# ProDoc_simpleCH552_typeA_finished.net
KiCad netlist of a schematic drawn in EasyEDA Pro
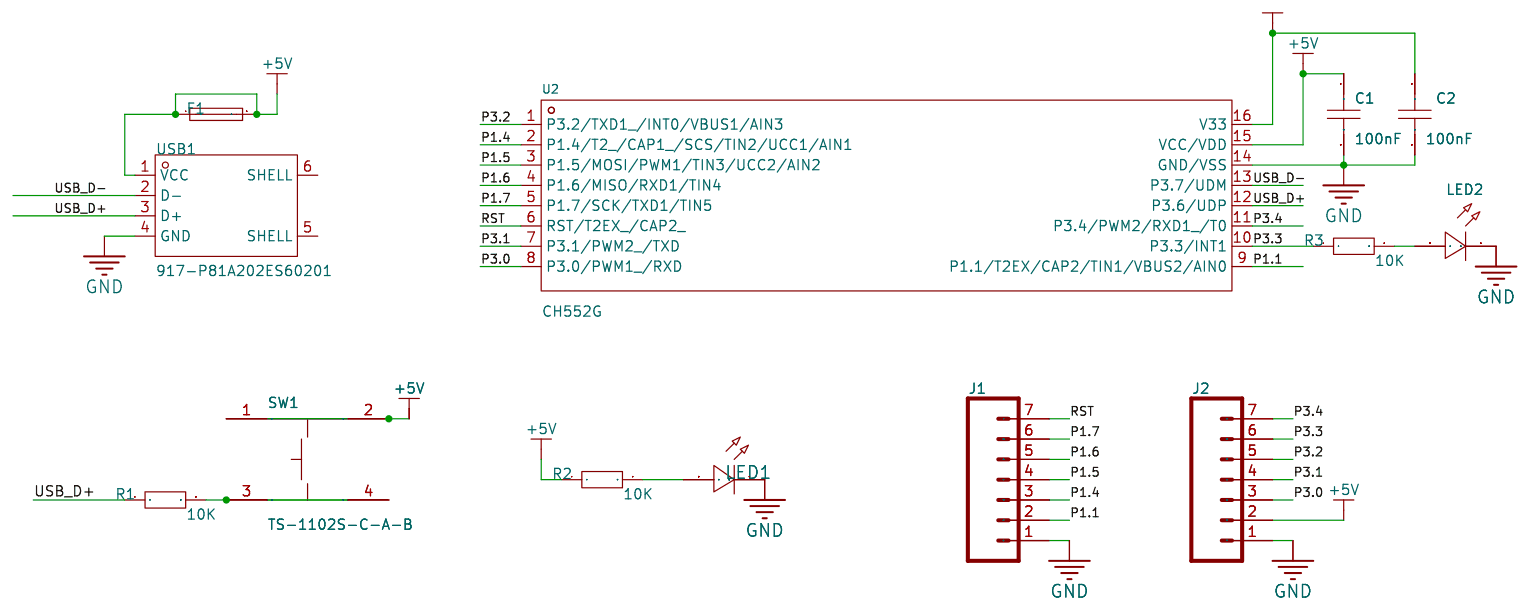
[diagram p0: schematic sheet]

(export (version "E")
  (design (tool "Eeschema 10.0.6"))
  (components
    (comp (ref "C1")
      (value "100nF")
      (footprint "easyedapro:C0805")
      (libsource (lib "easyedapro") (part "CAP"))
    )
    (comp (ref "C2")
      (value "100nF")
      (footprint "easyedapro:C0805")
      (libsource (lib "easyedapro") (part "CAP"))
    )
    (comp (ref "F1")
      (value "SF-1206S080-2")
      (footprint "easyedapro:F1206")
      (fields (field (name "Manufacturer") "BOURNS"))
      (libsource (lib "easyedapro") (part "SF-1206S080-2"))
    )
    (comp (ref "J1")
      (value "CONN_07NO_SILK")
      (footprint "easyedapro:1X07_NO_SILK")
      (libsource (lib "easyedapro") (part "SparkFun-Connectors_CONN_07_NO_SILK"))
    )
    (comp (ref "J2")
      (value "CONN_07NO_SILK")
      (footprint "easyedapro:1X07_NO_SILK")
      (libsource (lib "easyedapro") (part "SparkFun-Connectors_CONN_07_NO_SILK"))
    )
    (comp (ref "LED1")
      (value "~")
      (footprint "easyedapro:LED0805-RD_GREEN")
      (libsource (lib "easyedapro") (part "LED_R"))
    )
    (comp (ref "LED2")
      (value "~")
      (footprint "easyedapro:LED0805-RD_GREEN")
      (libsource (lib "easyedapro") (part "LED_G"))
    )
    (comp (ref "R1") (value "10K") (footprint "easyedapro:R0805") (libsource (lib "easyedapro") (part "Res")))
    (comp (ref "R2") (value "10K") (footprint "easyedapro:R0805") (libsource (lib "easyedapro") (part "Res")))
    (comp (ref "R3") (value "10K") (footprint "easyedapro:R0805") (libsource (lib "easyedapro") (part "Res")))
    (comp (ref "SW1")
      (value "TS-1102S-C-A-B")
      (footprint "easyedapro:KEY-SMD_4P-L6.0-W6.0-P4.50-LS8.6")
      (fields (field (name "Manufacturer") "XKB Connection(中国星坤)"))
      (libsource (lib "easyedapro") (part "TS-1102S-C-A-B"))
    )
    (comp (ref "U2")
      (value "CH552G")
      (footprint "easyedapro:SOP-16_L10.0-W3.9-P1.27-LS6.0-BL")
      (fields (field (name "Manufacturer") "WCH(南京沁恒)"))
      (libsource (lib "easyedapro") (part "CH552G"))
    )
    (comp (ref "USB1")
      (value "917-P81A202ES60201")
      (footprint "easyedapro:USB-A-SMD_917-P81A202ES60201")
      (fields (field (name "Manufacturer") "精拓金"))
      (libsource (lib "easyedapro") (part "917-P81A202ES60201"))
    )
  )
  (nets
    (net (code "1") (name "+5V") (class "Default")
      (node (ref "C1") (pin "1") (pinfunction "1_1") (pintype "input"))
      (node (ref "F1") (pin "1") (pinfunction "1_1") (pintype "unspecified"))
      (node (ref "F1") (pin "2") (pinfunction "2_2") (pintype "unspecified"))
      (node (ref "J2") (pin "2") (pinfunction "2_2") (pintype "unspecified"))
      (node (ref "R2") (pin "1") (pinfunction "1_1") (pintype "input"))
      (node (ref "SW1") (pin "1") (pinfunction "1_1") (pintype "unspecified"))
      (node (ref "SW1") (pin "2") (pinfunction "2_2") (pintype "unspecified"))
      (node (ref "U2") (pin "15") (pinfunction "VCC/VDD_15") (pintype "input"))
      (node (ref "USB1") (pin "1") (pinfunction "VCC_1") (pintype "unspecified"))
    )
    (net (code "2") (name "/P1.1") (class "Default")
      (node (ref "J1") (pin "2") (pinfunction "2_2") (pintype "unspecified"))
      (node (ref "U2") (pin "9") (pinfunction "P1.1/T2EX/CAP2/TIN1/VBUS2/AIN0_9") (pintype "input"))
    )
    (net (code "3") (name "/P1.4") (class "Default")
      (node (ref "J1") (pin "3") (pinfunction "3_3") (pintype "unspecified"))
      (node (ref "U2") (pin "2") (pinfunction "P1.4/T2_/CAP1_/SCS/TIN2/UCC1/AIN1_2") (pintype "input"))
    )
    (net (code "4") (name "/P1.5") (class "Default")
      (node (ref "J1") (pin "4") (pinfunction "4_4") (pintype "unspecified"))
      (node (ref "U2") (pin "3") (pinfunction "P1.5/MOSI/PWM1/TIN3/UCC2/AIN2_3") (pintype "input"))
    )
    (net (code "5") (name "/P1.6") (class "Default")
      (node (ref "J1") (pin "5") (pinfunction "5_5") (pintype "unspecified"))
      (node (ref "U2") (pin "4") (pinfunction "P1.6/MISO/RXD1/TIN4_4") (pintype "input"))
    )
    (net (code "6") (name "/P1.7") (class "Default")
      (node (ref "J1") (pin "6") (pinfunction "6_6") (pintype "unspecified"))
      (node (ref "U2") (pin "5") (pinfunction "P1.7/SCK/TXD1/TIN5_5") (pintype "input"))
    )
    (net (code "7") (name "/P3.0") (class "Default")
      (node (ref "J2") (pin "3") (pinfunction "3_3") (pintype "unspecified"))
      (node (ref "U2") (pin "8") (pinfunction "P3.0/PWM1_/RXD_8") (pintype "input"))
    )
    (net (code "8") (name "/P3.1") (class "Default")
      (node (ref "J2") (pin "4") (pinfunction "4_4") (pintype "unspecified"))
      (node (ref "U2") (pin "7") (pinfunction "P3.1/PWM2_/TXD_7") (pintype "input"))
    )
    (net (code "9") (name "/P3.2") (class "Default")
      (node (ref "J2") (pin "5") (pinfunction "5_5") (pintype "unspecified"))
      (node (ref "U2") (pin "1") (pinfunction "P3.2/TXD1_/INT0/VBUS1/AIN3_1") (pintype "input"))
    )
    (net (code "10") (name "/P3.3") (class "Default")
      (node (ref "J2") (pin "6") (pinfunction "6_6") (pintype "unspecified"))
      (node (ref "R3") (pin "1") (pinfunction "1_1") (pintype "input"))
      (node (ref "U2") (pin "10") (pinfunction "P3.3/INT1_10") (pintype "input"))
    )
    (net (code "11") (name "/P3.4") (class "Default")
      (node (ref "J2") (pin "7") (pinfunction "7_7") (pintype "unspecified"))
      (node (ref "U2") (pin "11") (pinfunction "P3.4/PWM2/RXD1_/T0_11") (pintype "input"))
    )
    (net (code "12") (name "/RST") (class "Default")
      (node (ref "J1") (pin "7") (pinfunction "7_7") (pintype "unspecified"))
      (node (ref "U2") (pin "6") (pinfunction "RST/T2EX_/CAP2__6") (pintype "input"))
    )
    (net (code "13") (name "/USB_D+") (class "Default")
      (node (ref "R1") (pin "1") (pinfunction "1_1") (pintype "input"))
      (node (ref "U2") (pin "12") (pinfunction "P3.6/UDP_12") (pintype "input"))
      (node (ref "USB1") (pin "3") (pinfunction "D+_3") (pintype "unspecified"))
    )
    (net (code "14") (name "/USB_D-") (class "Default")
      (node (ref "U2") (pin "13") (pinfunction "P3.7/UDM_13") (pintype "input"))
      (node (ref "USB1") (pin "2") (pinfunction "D-_2") (pintype "unspecified"))
    )
    (net (code "15") (name "3.3V") (class "Default")
      (node (ref "C2") (pin "1") (pinfunction "1_1") (pintype "input"))
      (node (ref "U2") (pin "16") (pinfunction "V33_16") (pintype "input"))
    )
    (net (code "16") (name "GND") (class "Default")
      (node (ref "C1") (pin "2") (pinfunction "2_2") (pintype "input"))
      (node (ref "C2") (pin "2") (pinfunction "2_2") (pintype "input"))
      (node (ref "J1") (pin "1") (pinfunction "1_1") (pintype "unspecified"))
      (node (ref "J2") (pin "1") (pinfunction "1_1") (pintype "unspecified"))
      (node (ref "LED1") (pin "1") (pinfunction "C_1") (pintype "input"))
      (node (ref "LED2") (pin "1") (pinfunction "C_1") (pintype "input"))
      (node (ref "U2") (pin "14") (pinfunction "GND/VSS_14") (pintype "input"))
      (node (ref "USB1") (pin "4") (pinfunction "GND_4") (pintype "unspecified"))
    )
    (net (code "17") (name "Net-(LED1-A)") (class "Default")
      (node (ref "LED1") (pin "2") (pinfunction "A_2") (pintype "input"))
      (node (ref "R2") (pin "2") (pinfunction "2_2") (pintype "input"))
    )
    (net (code "18") (name "Net-(LED2-A)") (class "Default")
      (node (ref "LED2") (pin "2") (pinfunction "A_2") (pintype "input"))
      (node (ref "R3") (pin "2") (pinfunction "2_2") (pintype "input"))
    )
    (net (code "19") (name "Net-(R1-Pad2)") (class "Default")
      (node (ref "R1") (pin "2") (pinfunction "2_2") (pintype "input"))
      (node (ref "SW1") (pin "3") (pinfunction "3_3") (pintype "unspecified"))
      (node (ref "SW1") (pin "4") (pinfunction "4_4") (pintype "unspecified"))
    )
    (net (code "20") (name "unconnected-(USB1-SHELL-Pad5)") (class "Default")
      (node (ref "USB1") (pin "5") (pinfunction "SHELL_5") (pintype "unspecified"))
    )
    (net (code "21") (name "unconnected-(USB1-SHELL-Pad6)") (class "Default")
      (node (ref "USB1") (pin "6") (pinfunction "SHELL_6") (pintype "unspecified"))
    )
  )
)
